# usb-hub-v0_2.net
KiCad netlist of a schematic drawn in EAGLE
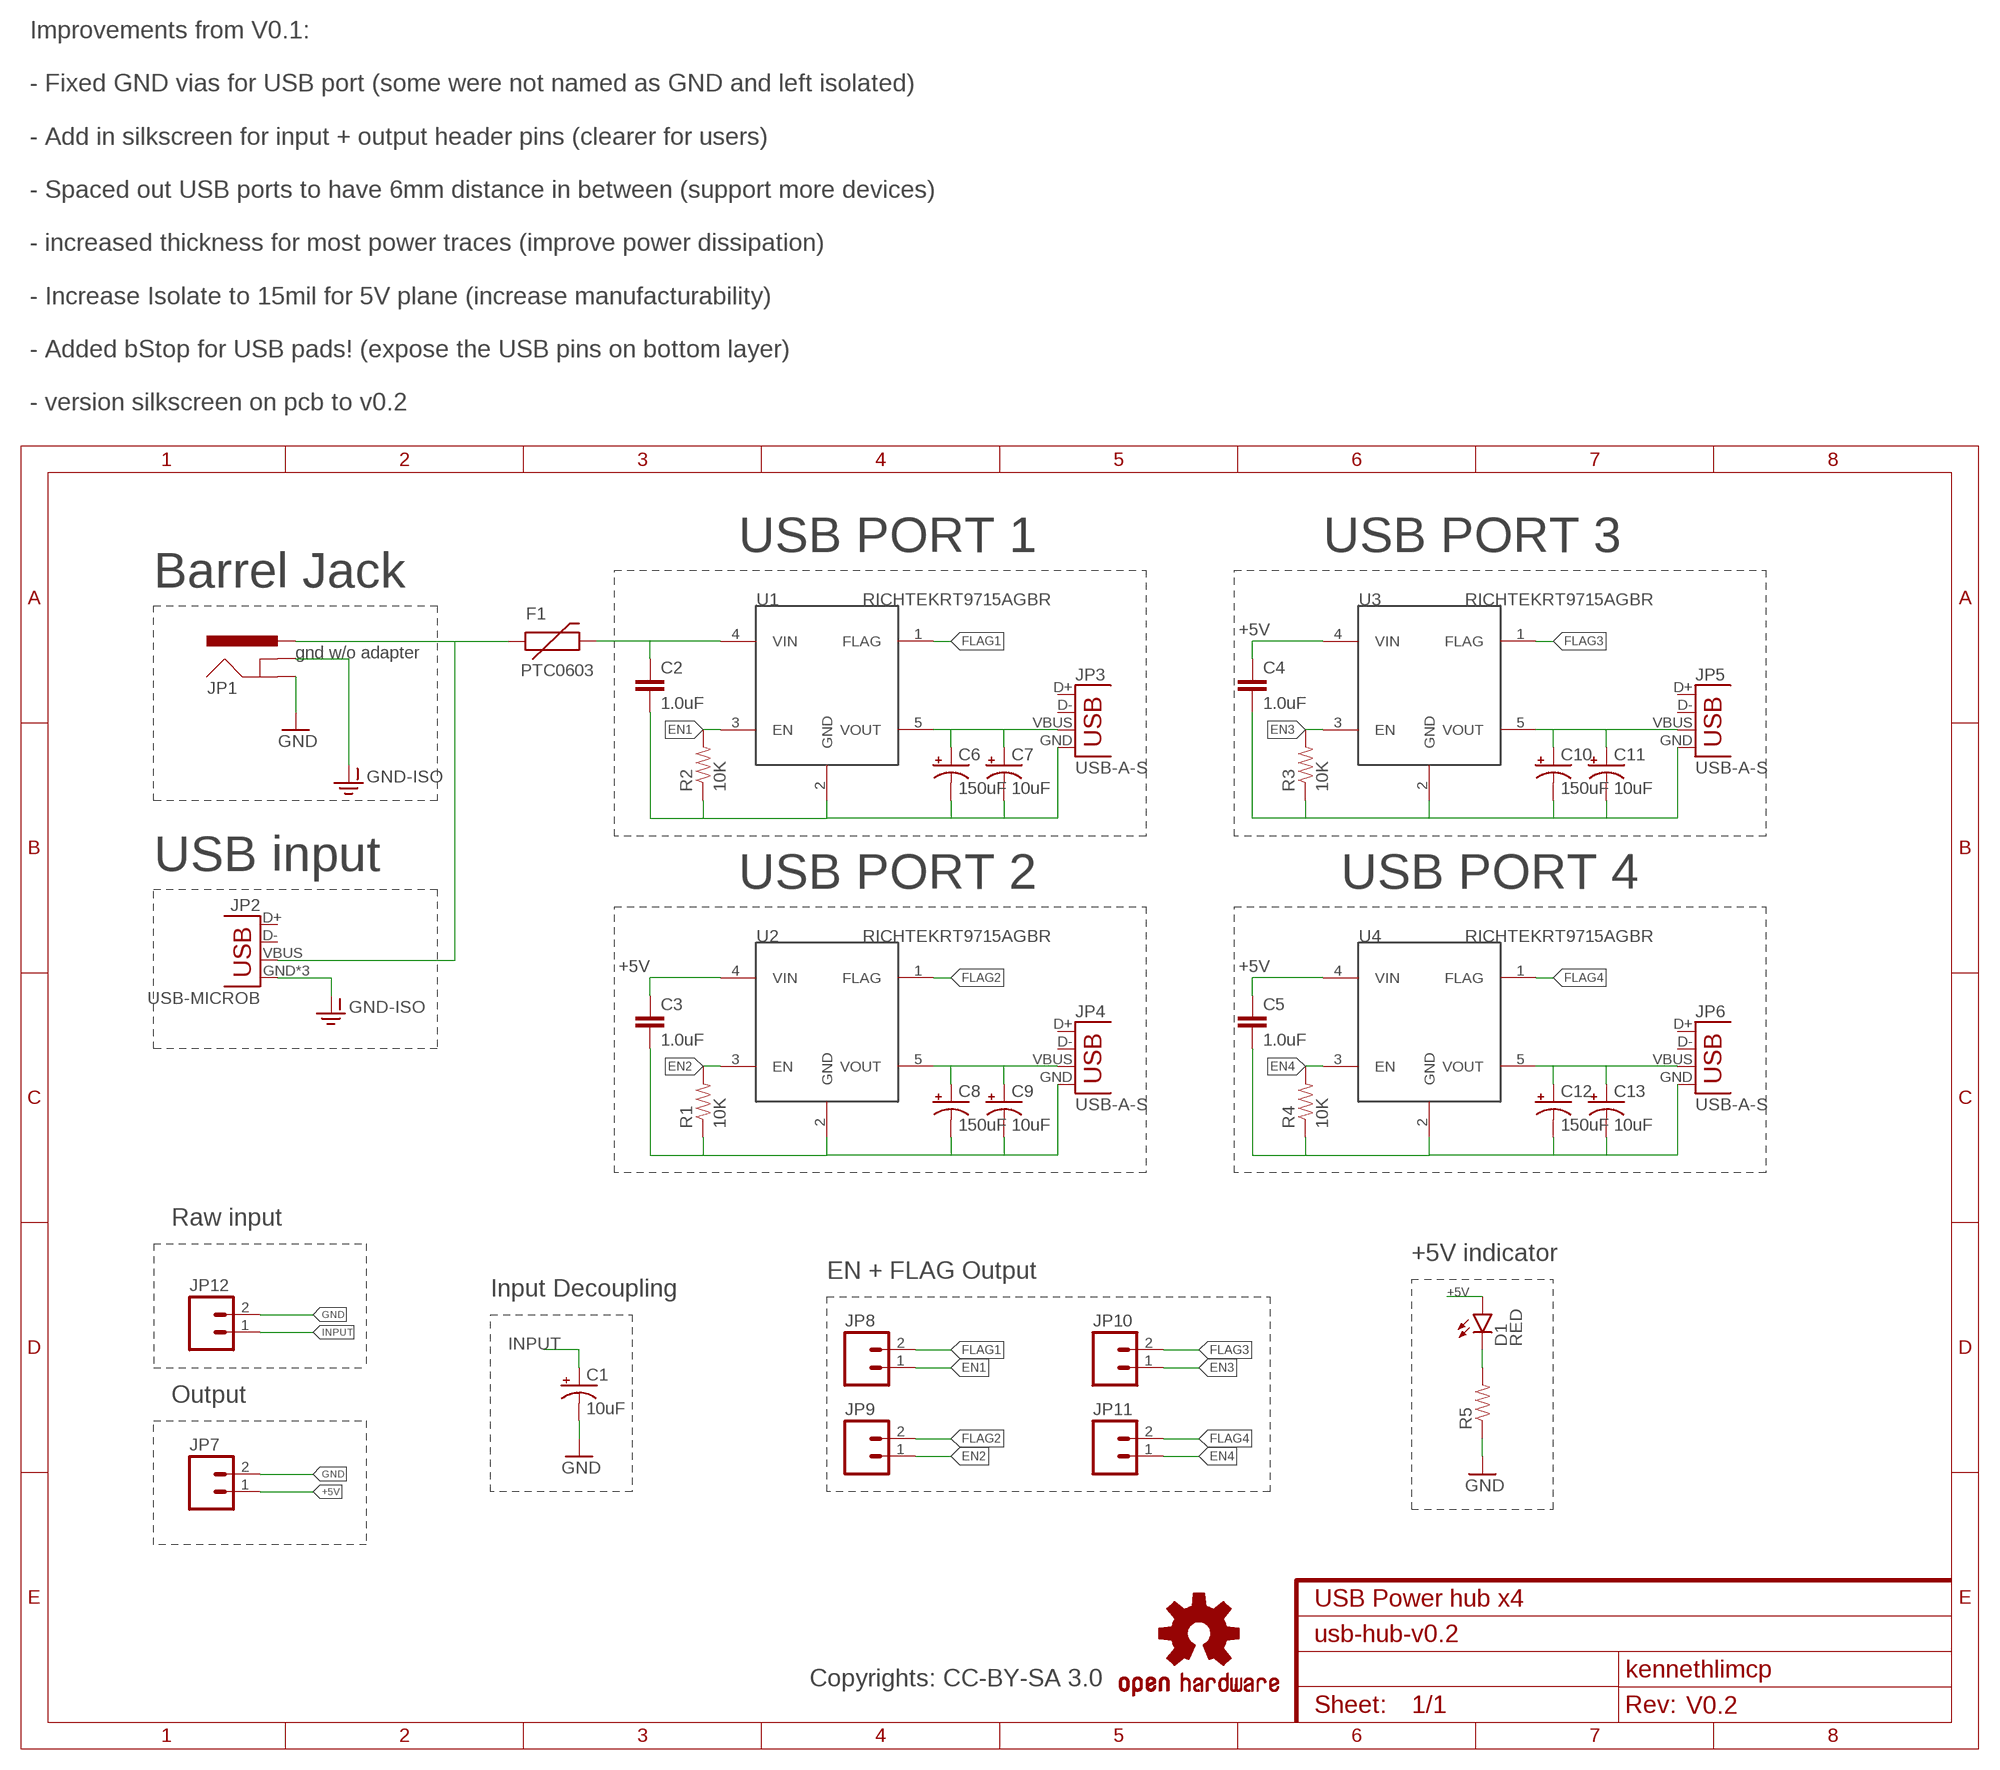
[diagram p0: schematic, sheet 1]

(export (version "E")
  (design (tool "Eeschema 10.0.6"))
  (components
    (comp (ref "C1")
      (value "10uF")
      (footprint "eagle-import:EIA3216")
      (libsource (lib "eagle-import") (part "10UF-16V-10%(TANT)"))
    )
    (comp (ref "C2")
      (value "1.0uF")
      (footprint "eagle-import:0603-CAP")
      (libsource (lib "eagle-import") (part "1.0UF-16V-10%(0603)"))
    )
    (comp (ref "C3")
      (value "1.0uF")
      (footprint "eagle-import:0603-CAP")
      (libsource (lib "eagle-import") (part "1.0UF-16V-10%(0603)"))
    )
    (comp (ref "C4")
      (value "1.0uF")
      (footprint "eagle-import:0603-CAP")
      (libsource (lib "eagle-import") (part "1.0UF-16V-10%(0603)"))
    )
    (comp (ref "C5")
      (value "1.0uF")
      (footprint "eagle-import:0603-CAP")
      (libsource (lib "eagle-import") (part "1.0UF-16V-10%(0603)"))
    )
    (comp (ref "C6")
      (value "150uF")
      (footprint "eagle-import:PANASONIC_D")
      (libsource (lib "eagle-import") (part "CAP_POLD"))
    )
    (comp (ref "C7")
      (value "10uF")
      (footprint "eagle-import:EIA3216")
      (libsource (lib "eagle-import") (part "10UF-16V-10%(TANT)"))
    )
    (comp (ref "C8")
      (value "150uF")
      (footprint "eagle-import:PANASONIC_D")
      (libsource (lib "eagle-import") (part "CAP_POLD"))
    )
    (comp (ref "C9")
      (value "10uF")
      (footprint "eagle-import:EIA3216")
      (libsource (lib "eagle-import") (part "10UF-16V-10%(TANT)"))
    )
    (comp (ref "C10")
      (value "150uF")
      (footprint "eagle-import:PANASONIC_D")
      (libsource (lib "eagle-import") (part "CAP_POLD"))
    )
    (comp (ref "C11")
      (value "10uF")
      (footprint "eagle-import:EIA3216")
      (libsource (lib "eagle-import") (part "10UF-16V-10%(TANT)"))
    )
    (comp (ref "C12")
      (value "150uF")
      (footprint "eagle-import:PANASONIC_D")
      (libsource (lib "eagle-import") (part "CAP_POLD"))
    )
    (comp (ref "C13")
      (value "10uF")
      (footprint "eagle-import:EIA3216")
      (libsource (lib "eagle-import") (part "10UF-16V-10%(TANT)"))
    )
    (comp (ref "D1")
      (value "RED")
      (footprint "eagle-import:LED-0603")
      (libsource (lib "eagle-import") (part "LED-RED0603"))
    )
    (comp (ref "F1")
      (value "PTC0603")
      (footprint "eagle-import:0603")
      (libsource (lib "eagle-import") (part "PTC0603"))
    )
    (comp (ref "JP1")
      (value "POWER_JACKPTH_LOCK")
      (footprint "eagle-import:POWER_JACK_PTH_LOCK")
      (libsource (lib "eagle-import") (part "POWER_JACKPTH_LOCK"))
    )
    (comp (ref "JP2")
      (value "USB-MICROB")
      (footprint "eagle-import:USB-MICROB")
      (libsource (lib "eagle-import") (part "USB-MICROB"))
    )
    (comp (ref "JP3")
      (value "USB-A-S")
      (footprint "eagle-import:USB-A-S")
      (libsource (lib "eagle-import") (part "USB-A-S"))
    )
    (comp (ref "JP4")
      (value "USB-A-S")
      (footprint "eagle-import:USB-A-S")
      (libsource (lib "eagle-import") (part "USB-A-S"))
    )
    (comp (ref "JP5")
      (value "USB-A-S")
      (footprint "eagle-import:USB-A-S")
      (libsource (lib "eagle-import") (part "USB-A-S"))
    )
    (comp (ref "JP6")
      (value "USB-A-S")
      (footprint "eagle-import:USB-A-S")
      (libsource (lib "eagle-import") (part "USB-A-S"))
    )
    (comp (ref "JP7")
      (value "M02PTH")
      (footprint "eagle-import:1X02")
      (libsource (lib "eagle-import") (part "M02PTH"))
    )
    (comp (ref "JP8")
      (value "M02PTH")
      (footprint "eagle-import:1X02")
      (libsource (lib "eagle-import") (part "M02PTH"))
    )
    (comp (ref "JP9")
      (value "M02PTH")
      (footprint "eagle-import:1X02")
      (libsource (lib "eagle-import") (part "M02PTH"))
    )
    (comp (ref "JP10")
      (value "M02PTH")
      (footprint "eagle-import:1X02")
      (libsource (lib "eagle-import") (part "M02PTH"))
    )
    (comp (ref "JP11")
      (value "M02PTH")
      (footprint "eagle-import:1X02")
      (libsource (lib "eagle-import") (part "M02PTH"))
    )
    (comp (ref "JP12")
      (value "M02PTH")
      (footprint "eagle-import:1X02")
      (libsource (lib "eagle-import") (part "M02PTH"))
    )
    (comp (ref "LOGO1")
      (value "OSHW-LOGOPAD")
      (footprint "eagle-import:OSHW-LOGO-M-PAD")
      (libsource (lib "eagle-import") (part "OSHW-LOGOPAD"))
    )
    (comp (ref "R1")
      (value "10K")
      (footprint "eagle-import:0402-RES")
      (libsource (lib "eagle-import") (part "RESISTOR0402"))
    )
    (comp (ref "R2")
      (value "10K")
      (footprint "eagle-import:0402-RES")
      (libsource (lib "eagle-import") (part "RESISTOR0402"))
    )
    (comp (ref "R3")
      (value "10K")
      (footprint "eagle-import:0402-RES")
      (libsource (lib "eagle-import") (part "RESISTOR0402"))
    )
    (comp (ref "R4")
      (value "10K")
      (footprint "eagle-import:0402-RES")
      (libsource (lib "eagle-import") (part "RESISTOR0402"))
    )
    (comp (ref "R5")
      (value "RESISTOR0402")
      (footprint "eagle-import:0402-RES")
      (libsource (lib "eagle-import") (part "RESISTOR0402"))
    )
    (comp (ref "U1")
      (value "RICHTEKRT9715AGBR")
      (footprint "eagle-import:SOT23-5")
      (libsource (lib "eagle-import") (part "RICHTEKRT9715AGBR"))
    )
    (comp (ref "U2")
      (value "RICHTEKRT9715AGBR")
      (footprint "eagle-import:SOT23-5")
      (libsource (lib "eagle-import") (part "RICHTEKRT9715AGBR"))
    )
    (comp (ref "U3")
      (value "RICHTEKRT9715AGBR")
      (footprint "eagle-import:SOT23-5")
      (libsource (lib "eagle-import") (part "RICHTEKRT9715AGBR"))
    )
    (comp (ref "U4")
      (value "RICHTEKRT9715AGBR")
      (footprint "eagle-import:SOT23-5")
      (libsource (lib "eagle-import") (part "RICHTEKRT9715AGBR"))
    )
  )
  (nets
    (net (code "1") (name "+5V") (class "Default")
      (node (ref "C2") (pin "1") (pinfunction "1_1") (pintype "passive"))
      (node (ref "C3") (pin "1") (pinfunction "1_1") (pintype "passive"))
      (node (ref "C4") (pin "1") (pinfunction "1_1") (pintype "passive"))
      (node (ref "C5") (pin "1") (pinfunction "1_1") (pintype "passive"))
      (node (ref "D1") (pin "A") (pinfunction "A_A") (pintype "passive"))
      (node (ref "F1") (pin "2") (pinfunction "2_2") (pintype "bidirectional"))
      (node (ref "JP7") (pin "1") (pinfunction "1_1") (pintype "passive"))
      (node (ref "U1") (pin "4") (pinfunction "VIN_4") (pintype "bidirectional"))
      (node (ref "U2") (pin "4") (pinfunction "VIN_4") (pintype "bidirectional"))
      (node (ref "U3") (pin "4") (pinfunction "VIN_4") (pintype "bidirectional"))
      (node (ref "U4") (pin "4") (pinfunction "VIN_4") (pintype "bidirectional"))
    )
    (net (code "2") (name "EN1") (class "Default")
      (node (ref "JP8") (pin "1") (pinfunction "1_1") (pintype "passive"))
      (node (ref "R2") (pin "2") (pinfunction "2_2") (pintype "passive"))
      (node (ref "U1") (pin "3") (pinfunction "EN_3") (pintype "bidirectional"))
    )
    (net (code "3") (name "EN2") (class "Default")
      (node (ref "JP9") (pin "1") (pinfunction "1_1") (pintype "passive"))
      (node (ref "R1") (pin "2") (pinfunction "2_2") (pintype "passive"))
      (node (ref "U2") (pin "3") (pinfunction "EN_3") (pintype "bidirectional"))
    )
    (net (code "4") (name "EN3") (class "Default")
      (node (ref "JP10") (pin "1") (pinfunction "1_1") (pintype "passive"))
      (node (ref "R3") (pin "2") (pinfunction "2_2") (pintype "passive"))
      (node (ref "U3") (pin "3") (pinfunction "EN_3") (pintype "bidirectional"))
    )
    (net (code "5") (name "EN4") (class "Default")
      (node (ref "JP11") (pin "1") (pinfunction "1_1") (pintype "passive"))
      (node (ref "R4") (pin "2") (pinfunction "2_2") (pintype "passive"))
      (node (ref "U4") (pin "3") (pinfunction "EN_3") (pintype "bidirectional"))
    )
    (net (code "6") (name "FLAG1") (class "Default")
      (node (ref "JP8") (pin "2") (pinfunction "2_2") (pintype "passive"))
      (node (ref "U1") (pin "1") (pinfunction "FLAG_1") (pintype "bidirectional"))
    )
    (net (code "7") (name "FLAG2") (class "Default")
      (node (ref "JP9") (pin "2") (pinfunction "2_2") (pintype "passive"))
      (node (ref "U2") (pin "1") (pinfunction "FLAG_1") (pintype "bidirectional"))
    )
    (net (code "8") (name "FLAG3") (class "Default")
      (node (ref "JP10") (pin "2") (pinfunction "2_2") (pintype "passive"))
      (node (ref "U3") (pin "1") (pinfunction "FLAG_1") (pintype "bidirectional"))
    )
    (net (code "9") (name "FLAG4") (class "Default")
      (node (ref "JP11") (pin "2") (pinfunction "2_2") (pintype "passive"))
      (node (ref "U4") (pin "1") (pinfunction "FLAG_1") (pintype "bidirectional"))
    )
    (net (code "10") (name "GND") (class "Default")
      (node (ref "C1") (pin "C") (pinfunction "-_C") (pintype "passive"))
      (node (ref "C10") (pin "-") (pinfunction "-_-") (pintype "passive"))
      (node (ref "C11") (pin "C") (pinfunction "-_C") (pintype "passive"))
      (node (ref "C12") (pin "-") (pinfunction "-_-") (pintype "passive"))
      (node (ref "C13") (pin "C") (pinfunction "-_C") (pintype "passive"))
      (node (ref "C2") (pin "2") (pinfunction "2_2") (pintype "passive"))
      (node (ref "C3") (pin "2") (pinfunction "2_2") (pintype "passive"))
      (node (ref "C4") (pin "2") (pinfunction "2_2") (pintype "passive"))
      (node (ref "C5") (pin "2") (pinfunction "2_2") (pintype "passive"))
      (node (ref "C6") (pin "-") (pinfunction "-_-") (pintype "passive"))
      (node (ref "C7") (pin "C") (pinfunction "-_C") (pintype "passive"))
      (node (ref "C8") (pin "-") (pinfunction "-_-") (pintype "passive"))
      (node (ref "C9") (pin "C") (pinfunction "-_C") (pintype "passive"))
      (node (ref "JP1") (pin "GND") (pinfunction "GND_GND") (pintype "bidirectional"))
      (node (ref "JP12") (pin "2") (pinfunction "2_2") (pintype "passive"))
      (node (ref "JP3") (pin "GND") (pinfunction "GND_GND") (pintype "bidirectional"))
      (node (ref "JP4") (pin "GND") (pinfunction "GND_GND") (pintype "bidirectional"))
      (node (ref "JP5") (pin "GND") (pinfunction "GND_GND") (pintype "bidirectional"))
      (node (ref "JP6") (pin "GND") (pinfunction "GND_GND") (pintype "bidirectional"))
      (node (ref "JP7") (pin "2") (pinfunction "2_2") (pintype "passive"))
      (node (ref "R1") (pin "1") (pinfunction "1_1") (pintype "passive"))
      (node (ref "R2") (pin "1") (pinfunction "1_1") (pintype "passive"))
      (node (ref "R3") (pin "1") (pinfunction "1_1") (pintype "passive"))
      (node (ref "R4") (pin "1") (pinfunction "1_1") (pintype "passive"))
      (node (ref "R5") (pin "1") (pinfunction "1_1") (pintype "passive"))
      (node (ref "U1") (pin "2") (pinfunction "GND_2") (pintype "bidirectional"))
      (node (ref "U2") (pin "2") (pinfunction "GND_2") (pintype "bidirectional"))
      (node (ref "U3") (pin "2") (pinfunction "GND_2") (pintype "bidirectional"))
      (node (ref "U4") (pin "2") (pinfunction "GND_2") (pintype "bidirectional"))
    )
    (net (code "11") (name "GND-ISO") (class "Default")
      (node (ref "JP1") (pin "GNDBREAK") (pinfunction "GNDBREAK_GNDBREAK") (pintype "bidirectional"))
      (node (ref "JP2") (pin "GND") (pinfunction "GND_GND") (pintype "bidirectional"))
      (node (ref "JP2") (pin "MT1") (pinfunction "GND_MT1") (pintype "bidirectional"))
      (node (ref "JP2") (pin "MT2") (pinfunction "GND_MT2") (pintype "bidirectional"))
    )
    (net (code "12") (name "INPUT") (class "Default")
      (node (ref "C1") (pin "A") (pinfunction "+_A") (pintype "passive"))
      (node (ref "F1") (pin "1") (pinfunction "1_1") (pintype "bidirectional"))
      (node (ref "JP1") (pin "PWR") (pinfunction "PWR_PWR") (pintype "bidirectional"))
      (node (ref "JP12") (pin "1") (pinfunction "1_1") (pintype "passive"))
      (node (ref "JP2") (pin "VBUS") (pinfunction "VBUS_VBUS") (pintype "bidirectional"))
    )
    (net (code "13") (name "Net-(C7-+)") (class "Default")
      (node (ref "C6") (pin "+") (pinfunction "+_+") (pintype "passive"))
      (node (ref "C7") (pin "A") (pinfunction "+_A") (pintype "passive"))
      (node (ref "JP3") (pin "VBUS") (pinfunction "VBUS_VBUS") (pintype "bidirectional"))
      (node (ref "U1") (pin "5") (pinfunction "VOUT_5") (pintype "bidirectional"))
    )
    (net (code "14") (name "Net-(C9-+)") (class "Default")
      (node (ref "C8") (pin "+") (pinfunction "+_+") (pintype "passive"))
      (node (ref "C9") (pin "A") (pinfunction "+_A") (pintype "passive"))
      (node (ref "JP4") (pin "VBUS") (pinfunction "VBUS_VBUS") (pintype "bidirectional"))
      (node (ref "U2") (pin "5") (pinfunction "VOUT_5") (pintype "bidirectional"))
    )
    (net (code "15") (name "Net-(C11-+)") (class "Default")
      (node (ref "C10") (pin "+") (pinfunction "+_+") (pintype "passive"))
      (node (ref "C11") (pin "A") (pinfunction "+_A") (pintype "passive"))
      (node (ref "JP5") (pin "VBUS") (pinfunction "VBUS_VBUS") (pintype "bidirectional"))
      (node (ref "U3") (pin "5") (pinfunction "VOUT_5") (pintype "bidirectional"))
    )
    (net (code "16") (name "Net-(C13-+)") (class "Default")
      (node (ref "C12") (pin "+") (pinfunction "+_+") (pintype "passive"))
      (node (ref "C13") (pin "A") (pinfunction "+_A") (pintype "passive"))
      (node (ref "JP6") (pin "VBUS") (pinfunction "VBUS_VBUS") (pintype "bidirectional"))
      (node (ref "U4") (pin "5") (pinfunction "VOUT_5") (pintype "bidirectional"))
    )
    (net (code "17") (name "Net-(D1-PadC)") (class "Default")
      (node (ref "D1") (pin "C") (pinfunction "C_C") (pintype "passive"))
      (node (ref "R5") (pin "2") (pinfunction "2_2") (pintype "passive"))
    )
    (net (code "18") (name "unconnected-(JP2-PadD+)") (class "Default")
      (node (ref "JP2") (pin "D+") (pinfunction "D+_D+") (pintype "bidirectional"))
    )
    (net (code "19") (name "unconnected-(JP2-PadD-)") (class "Default")
      (node (ref "JP2") (pin "D-") (pinfunction "D-_D-") (pintype "bidirectional"))
    )
    (net (code "20") (name "unconnected-(JP3-PadD+)") (class "Default")
      (node (ref "JP3") (pin "D+") (pinfunction "D+_D+") (pintype "bidirectional"))
    )
    (net (code "21") (name "unconnected-(JP3-PadD-)") (class "Default")
      (node (ref "JP3") (pin "D-") (pinfunction "D-_D-") (pintype "bidirectional"))
    )
    (net (code "22") (name "unconnected-(JP4-PadD+)") (class "Default")
      (node (ref "JP4") (pin "D+") (pinfunction "D+_D+") (pintype "bidirectional"))
    )
    (net (code "23") (name "unconnected-(JP4-PadD-)") (class "Default")
      (node (ref "JP4") (pin "D-") (pinfunction "D-_D-") (pintype "bidirectional"))
    )
    (net (code "24") (name "unconnected-(JP5-PadD+)") (class "Default")
      (node (ref "JP5") (pin "D+") (pinfunction "D+_D+") (pintype "bidirectional"))
    )
    (net (code "25") (name "unconnected-(JP5-PadD-)") (class "Default")
      (node (ref "JP5") (pin "D-") (pinfunction "D-_D-") (pintype "bidirectional"))
    )
    (net (code "26") (name "unconnected-(JP6-PadD+)") (class "Default")
      (node (ref "JP6") (pin "D+") (pinfunction "D+_D+") (pintype "bidirectional"))
    )
    (net (code "27") (name "unconnected-(JP6-PadD-)") (class "Default")
      (node (ref "JP6") (pin "D-") (pinfunction "D-_D-") (pintype "bidirectional"))
    )
  )
)
